# P3V3_PP5V_GESTION.net
KiCad netlist of a schematic drawn in Altium Designer
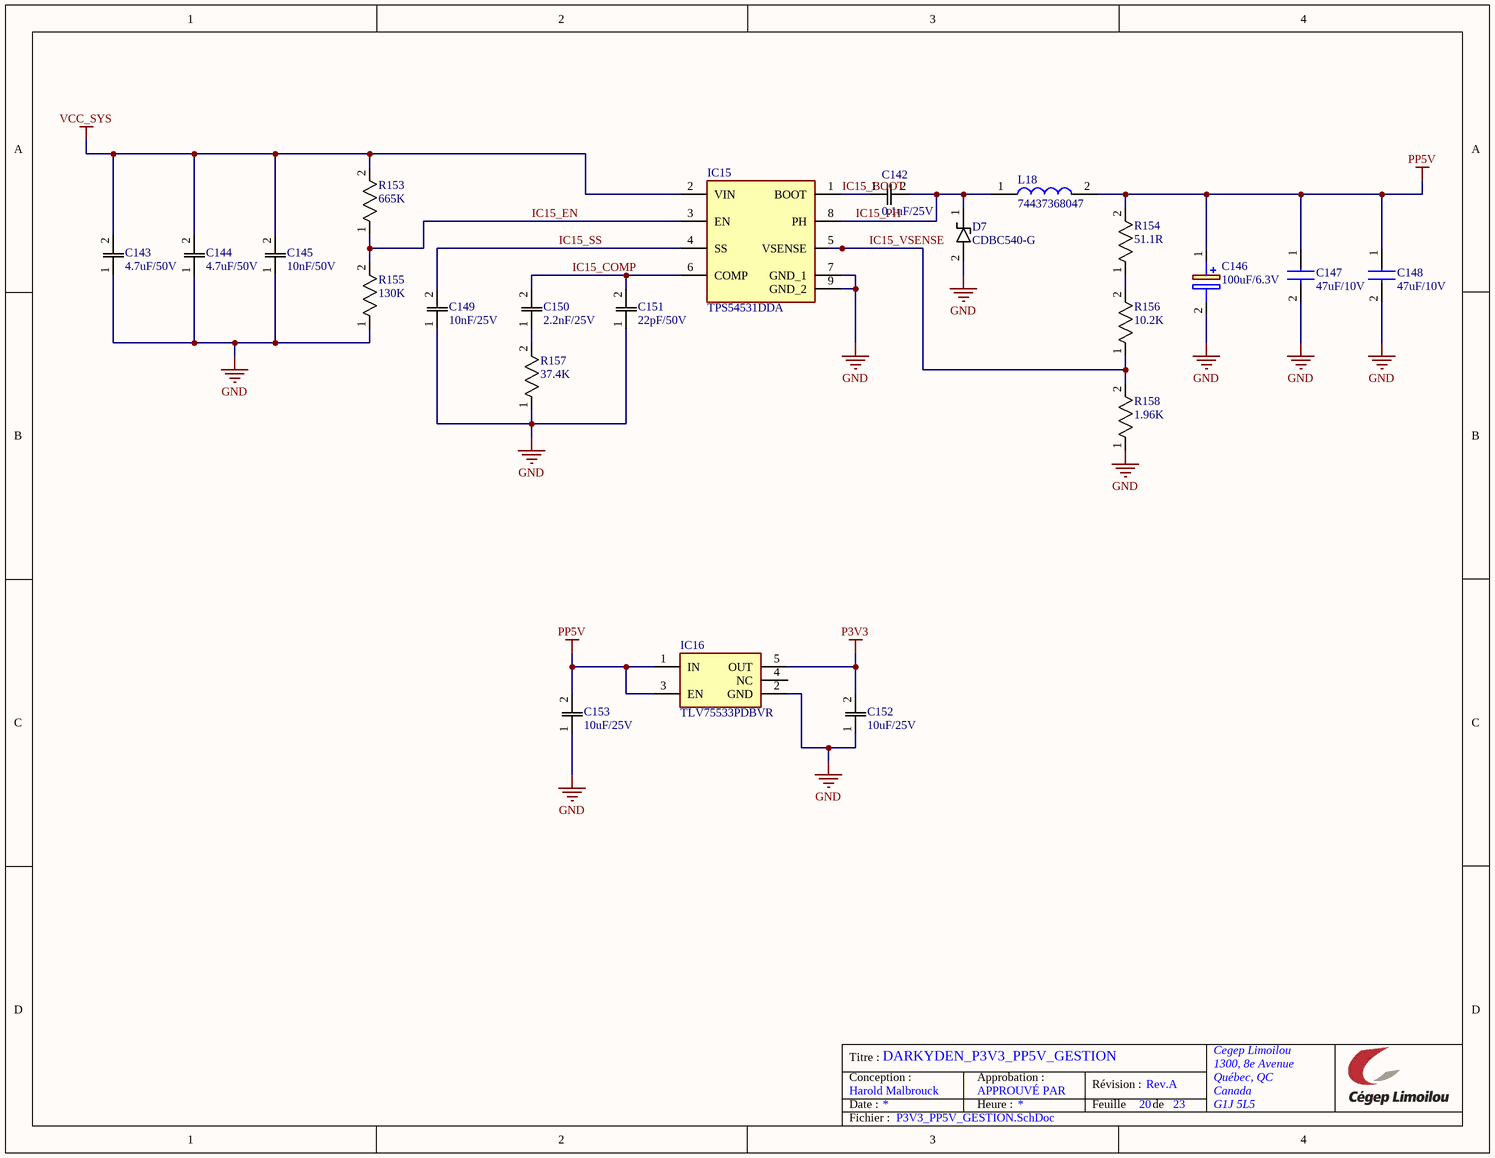
[diagram p0: P3V3_PP5V_GESTION.SchDoc]

(export (version "E")
  (design (tool "Eeschema 10.0.6"))
  (components
    (comp (ref "C142")
      (value "0.1uF/25V")
      (footprint "c0805")
      (description "0.1uF 25V X7R 10% SMD 0805 125C Plastic T/R")
      (fields
        (field (name "MANUFACTURER") "KEMET")
        (field (name "MANUFACTURER PART NUMBER") "C0805C104K3RACTU")
      )
      (libsource (lib "DARKYDEN") (part "C0805C104K3RACTU"))
    )
    (comp (ref "C143")
      (value "4.7uF/50V")
      (footprint "c0805")
      (description "4.7uF/50V X5R 卤10% 0805 Multilayer Ceramic Capacitors MLCC - SMD/SMT ROHS")
      (fields
        (field (name "MANUFACTURER") "TDK")
        (field (name "MANUFACTURER PART NUMBER") "CGA4J3X5R1H475K125AB")
      )
      (libsource (lib "DARKYDEN") (part "CGA4J3X5R1H475K125AB"))
    )
    (comp (ref "C144")
      (value "4.7uF/50V")
      (footprint "c0805")
      (description "4.7uF/50V X5R 卤10% 0805 Multilayer Ceramic Capacitors MLCC - SMD/SMT ROHS")
      (fields
        (field (name "MANUFACTURER") "TDK")
        (field (name "MANUFACTURER PART NUMBER") "CGA4J3X5R1H475K125AB")
      )
      (libsource (lib "DARKYDEN") (part "CGA4J3X5R1H475K125AB"))
    )
    (comp (ref "C145")
      (value "10nF/50V")
      (footprint "c0805")
      (description "10nF/50V X7R 0805 10%")
      (fields
        (field (name "MANUFACTURER") "KEMET")
        (field (name "MANUFACTURER PART NUMBER") "C0805C103K5RACTU")
      )
      (libsource (lib "DARKYDEN") (part "C0805C103K5RACTU"))
    )
    (comp (ref "C146")
      (value "100uF/6.3V")
      (footprint "SamacSys:T520B")
      (description "100uF / 6.3VDC B CASE 20%  Cap Tant Polymer SMD 3528-21 0.015 Ohm 105C T/R")
      (fields
        (field (name "MANUFACTURER_PART_NUMBER") "T520B107M006ATE015")
        (field (name "MOUSER PART NUMBER") "80-T520B107M6ATE15")
      )
      (libsource (lib "SamacSys") (part "T520B107M006ATE015"))
    )
    (comp (ref "C147")
      (value "47uF/10V")
      (footprint "SamacSys:CAPC3225X270N")
      (description "Multilayer Ceramic Capacitor, 47 uF, 10 V, ï¿½ 10%, X5R, 1210 [3225 Metric]")
      (fields
        (field (name "MANUFACTURER_PART_NUMBER") "GRM32ER61A476KE20L")
        (field (name "MOUSER PART NUMBER") "81-GRM32ER61A476KE20")
      )
      (libsource (lib "SamacSys") (part "GRM32ER61A476KE20L"))
    )
    (comp (ref "C148")
      (value "47uF/10V")
      (footprint "SamacSys:CAPC3225X270N")
      (description "Multilayer Ceramic Capacitor, 47 uF, 10 V, ï¿½ 10%, X5R, 1210 [3225 Metric]")
      (fields
        (field (name "MANUFACTURER_PART_NUMBER") "GRM32ER61A476KE20L")
        (field (name "MOUSER PART NUMBER") "81-GRM32ER61A476KE20")
      )
      (libsource (lib "SamacSys") (part "GRM32ER61A476KE20L"))
    )
    (comp (ref "C149")
      (value "10nF/25V")
      (footprint "C0805")
      (description "0.01uF 25V X7R 10% SMD 0805 125C Paper T/R")
      (fields
        (field (name "MANUFACTURER_PART_NUMBER") "C0805C103K3RACTU")
        (field (name "MOUSER PART NUMBER") "80-C0805C103K3R")
      )
      (libsource (lib "DARKYDEN") (part "C0805C103K3RACTU"))
    )
    (comp (ref "C150")
      (value "2.2nF/25V")
      (footprint "C0805")
      (description "2.2nF ±10% 25V Ceramic Capacitor C0G, NP0 0805 (2012 Metric)")
      (fields
        (field (name "MANUFACTURER") "KEMET")
        (field (name "MANUFACTURER PART NUMBER") "C0805C222K3GECTU")
      )
      (libsource (lib "DARKYDEN") (part "C0805C222K3GECTU"))
    )
    (comp (ref "C151")
      (value "22pF/50V")
      (footprint "C0805")
      (description "Cap Ceramic 22pF 50V X7R 5% Pad SMD 0805 125°C T/R")
      (fields
        (field (name "MANUFACTURER") "KEMET")
        (field (name "MANUFACTURER PART NUMBER") "C0805C220J5RACTU")
      )
      (libsource (lib "DARKYDEN") (part "C0805C220J5RACTU"))
    )
    (comp (ref "C152")
      (value "10uF/25V")
      (footprint "C0805")
      (description "10uF / 25 VDC, +85degC, X5R Dielec, +/-10% ¦ KEMET C0805C106K3PACTU 0805")
      (fields
        (field (name "MANUFACTURER") "KEMET")
        (field (name "MANUFACTURER PART NUMBER") "C0805C106K3PACTU")
      )
      (libsource (lib "DARKYDEN") (part "C0805C106K3PACTU"))
    )
    (comp (ref "C153")
      (value "10uF/25V")
      (footprint "C0805")
      (description "10uF / 25 VDC, +85degC, X5R Dielec, +/-10% ¦ KEMET C0805C106K3PACTU 0805")
      (fields
        (field (name "MANUFACTURER") "KEMET")
        (field (name "MANUFACTURER PART NUMBER") "C0805C106K3PACTU")
      )
      (libsource (lib "DARKYDEN") (part "C0805C106K3PACTU"))
    )
    (comp (ref "D7")
      (value "CDBC540-G")
      (footprint "SamacSys:DIOM8059X290N")
      (description "Schottky Diode 40V 5A 2-Pin DO-214AB (SMC) CDBC540-G SMT")
      (fields (field (name "MOUSER PART NUMBER") "750-CDBC540-G") (field (name "MANUFACTURER") "Comchip"))
      (libsource (lib "SamacSys") (part "CDBC540-G"))
    )
    (comp (ref "IC15")
      (value "TPS54531DDA")
      (footprint "SamacSys:SOIC127P600X170-9N")
      (fields (field (name "MOUSER PART NUMBER") "595-TPS54531DDA"))
      (libsource (lib "SamacSys") (part "TPS54531DDA"))
    )
    (comp (ref "IC16")
      (value "TLV75533PDBVR")
      (footprint "SamacSys:SOT95P280X145-5N")
      (description "500mA high-PSRR low-IQ low-dropout voltage regulator with enable 5-SOT-23 -40 to 125")
      (fields
        (field (name "MOUSER PART NUMBER") "595-TLV75533PDBVR")
        (field (name "MANUFACTURER") "Texas Instruments")
      )
      (libsource (lib "SamacSys") (part "TLV75533PDBVR"))
    )
    (comp (ref "L18")
      (value "74437368047")
      (footprint "SamacSys:WE-LHMI_104048")
      (fields
        (field (name "MOUSER PART NUMBER") "710-74437368047")
        (field (name "MANUFACTURER") "Wurth Electronics")
        (field (name "TOLERANCE") "20%")
      )
      (libsource (lib "SamacSys") (part "74437368047"))
    )
    (comp (ref "R153")
      (value "665K")
      (footprint "RESC1608X55N")
      (description "665 kOhm, ± 1%, 100 mW, 0603 [1608 Metric], Thick Film, Precision")
      (fields
        (field (name "MANUFACTURER") "Panasonic")
        (field (name "MANUFACTURER PART NUMBER") "ERJ-3EKF6653V")
      )
      (libsource (lib "DARKYDEN") (part "ERJ-3EKF6653V"))
    )
    (comp (ref "R154")
      (value "51.1R")
      (footprint "SamacSys:RESC1608X55N")
      (description "51.1 Ohm 1% 0.1W(1/10W) ±100ppm/C Pad SMD T/R Automotive AEC-Q200")
      (fields
        (field (name "MANUFACTURER_PART_NUMBER") "ERJ-3EKF51R1V")
        (field (name "MOUSER PART NUMBER") "667-ERJ-3EKF51R1V")
      )
      (libsource (lib "DARKYDEN") (part "ERJ-3EKF51R1V"))
    )
    (comp (ref "R155")
      (value "130K")
      (footprint "RESC1608X55N")
      (description "130K Ohm 1% 0.1W Res Thick Film 0603 ±100ppm/°C Molded SMD Punched Carrier T/R")
      (fields
        (field (name "MANUFACTURER") "Panasonic")
        (field (name "MANUFACTURER PART NUMBER") "ERJ-3EKF1303V")
      )
      (libsource (lib "DARKYDEN") (part "ERJ-3EKF1303V"))
    )
    (comp (ref "R156")
      (value "10.2K")
      (footprint "SamacSys:RESC1608X55N")
      (description "10.2 kOhm, ± 1%, 100 mW, 0603 [1608 Metric], Thick Film, Precision")
      (fields
        (field (name "MANUFACTURER_PART_NUMBER") "ERJ-3EKF1022V")
        (field (name "MOUSER PART NUMBER") "667-ERJ-3EKF1022V")
      )
      (libsource (lib "DARKYDEN") (part "ERJ-3EKF1022V"))
    )
    (comp (ref "R157")
      (value "37.4K")
      (footprint "RESC1608X55N")
      (description "37.4K Ohm 1% 1/10W ±100ppm/°C Molded SMD Punched Carrier T/R")
      (fields
        (field (name "MANUFACTURER") "Panasonic")
        (field (name "MANUFACTURER PART NUMBER") "ERJ-3EKF3742V")
      )
      (libsource (lib "DARKYDEN") (part "ERJ-3EKF3742V"))
    )
    (comp (ref "R158")
      (value "1.96K")
      (footprint "RESC1608X55N")
      (description "1.96K Ohm 1% 1/10W ±100ppm/°C Molded SMD Punched Carrier T/R")
      (fields
        (field (name "MANUFACTURER") "Panasonic")
        (field (name "MANUFACTURER PART NUMBER") "ERJ-3EKF1961V")
      )
      (libsource (lib "DARKYDEN") (part "ERJ-3EKF1961V"))
    )
  )
  (nets
    (net (code "1") (name "/IC15_BOOT") (class "Default")
      (node (ref "C142") (pin "1") (pinfunction "1_1") (pintype "passive"))
      (node (ref "IC15") (pin "1") (pinfunction "BOOT_1") (pintype "passive"))
    )
    (net (code "2") (name "/IC15_COMP") (class "Default")
      (node (ref "C150") (pin "2") (pinfunction "2_2") (pintype "passive"))
      (node (ref "C151") (pin "2") (pinfunction "2_2") (pintype "passive"))
      (node (ref "IC15") (pin "6") (pinfunction "COMP_6") (pintype "passive"))
    )
    (net (code "3") (name "/IC15_EN") (class "Default")
      (node (ref "IC15") (pin "3") (pinfunction "EN_3") (pintype "passive"))
      (node (ref "R153") (pin "1") (pinfunction "1_1") (pintype "passive"))
      (node (ref "R155") (pin "2") (pinfunction "2_2") (pintype "passive"))
    )
    (net (code "4") (name "/IC15_PH") (class "Default")
      (node (ref "C142") (pin "2") (pinfunction "2_2") (pintype "passive"))
      (node (ref "D7") (pin "1") (pinfunction "K_1") (pintype "passive"))
      (node (ref "IC15") (pin "8") (pinfunction "PH_8") (pintype "passive"))
      (node (ref "L18") (pin "1") (pinfunction "1_1") (pintype "passive"))
    )
    (net (code "5") (name "/IC15_SS") (class "Default")
      (node (ref "C149") (pin "2") (pinfunction "2_2") (pintype "passive"))
      (node (ref "IC15") (pin "4") (pinfunction "SS_4") (pintype "passive"))
    )
    (net (code "6") (name "/IC15_VSENSE") (class "Default")
      (node (ref "IC15") (pin "5") (pinfunction "VSENSE_5") (pintype "passive"))
      (node (ref "R156") (pin "1") (pinfunction "1_1") (pintype "passive"))
      (node (ref "R158") (pin "2") (pinfunction "2_2") (pintype "passive"))
    )
    (net (code "7") (name "GND") (class "Default")
      (node (ref "C143") (pin "1") (pinfunction "1_1") (pintype "passive"))
      (node (ref "C144") (pin "1") (pinfunction "1_1") (pintype "passive"))
      (node (ref "C145") (pin "1") (pinfunction "1_1") (pintype "passive"))
      (node (ref "C146") (pin "2") (pinfunction "-_2") (pintype "passive"))
      (node (ref "C147") (pin "2") (pinfunction "2_2") (pintype "passive"))
      (node (ref "C148") (pin "2") (pinfunction "2_2") (pintype "passive"))
      (node (ref "C149") (pin "1") (pinfunction "1_1") (pintype "passive"))
      (node (ref "C151") (pin "1") (pinfunction "1_1") (pintype "passive"))
      (node (ref "C152") (pin "1") (pinfunction "1_1") (pintype "passive"))
      (node (ref "C153") (pin "1") (pinfunction "1_1") (pintype "passive"))
      (node (ref "D7") (pin "2") (pinfunction "A_2") (pintype "passive"))
      (node (ref "IC15") (pin "7") (pinfunction "GND_1_7") (pintype "passive"))
      (node (ref "IC15") (pin "9") (pinfunction "GND_2_9") (pintype "passive"))
      (node (ref "IC16") (pin "2") (pinfunction "GND_2") (pintype "passive"))
      (node (ref "R155") (pin "1") (pinfunction "1_1") (pintype "passive"))
      (node (ref "R157") (pin "1") (pinfunction "1_1") (pintype "passive"))
      (node (ref "R158") (pin "1") (pinfunction "1_1") (pintype "passive"))
    )
    (net (code "8") (name "Net-(C150-Pad1)") (class "Default")
      (node (ref "C150") (pin "1") (pinfunction "1_1") (pintype "passive"))
      (node (ref "R157") (pin "2") (pinfunction "2_2") (pintype "passive"))
    )
    (net (code "9") (name "Net-(R154-Pad1)") (class "Default")
      (node (ref "R154") (pin "1") (pinfunction "1_1") (pintype "passive"))
      (node (ref "R156") (pin "2") (pinfunction "2_2") (pintype "passive"))
    )
    (net (code "10") (name "P3V3") (class "Default")
      (node (ref "C152") (pin "2") (pinfunction "2_2") (pintype "passive"))
      (node (ref "IC16") (pin "5") (pinfunction "OUT_5") (pintype "passive"))
    )
    (net (code "11") (name "PP5V") (class "Default")
      (node (ref "C146") (pin "1") (pinfunction "+_1") (pintype "passive"))
      (node (ref "C147") (pin "1") (pinfunction "1_1") (pintype "passive"))
      (node (ref "C148") (pin "1") (pinfunction "1_1") (pintype "passive"))
      (node (ref "C153") (pin "2") (pinfunction "2_2") (pintype "passive"))
      (node (ref "IC16") (pin "1") (pinfunction "IN_1") (pintype "passive"))
      (node (ref "IC16") (pin "3") (pinfunction "EN_3") (pintype "passive"))
      (node (ref "L18") (pin "2") (pinfunction "2_2") (pintype "passive"))
      (node (ref "R154") (pin "2") (pinfunction "2_2") (pintype "passive"))
    )
    (net (code "12") (name "VCC_SYS") (class "Default")
      (node (ref "C143") (pin "2") (pinfunction "2_2") (pintype "passive"))
      (node (ref "C144") (pin "2") (pinfunction "2_2") (pintype "passive"))
      (node (ref "C145") (pin "2") (pinfunction "2_2") (pintype "passive"))
      (node (ref "IC15") (pin "2") (pinfunction "VIN_2") (pintype "passive"))
      (node (ref "R153") (pin "2") (pinfunction "2_2") (pintype "passive"))
    )
    (net (code "13") (name "unconnected-(IC16-NC-Pad4)") (class "Default")
      (node (ref "IC16") (pin "4") (pinfunction "NC_4") (pintype "passive"))
    )
  )
)
